# capacitor.net
KiCad netlist of a schematic drawn in EAGLE
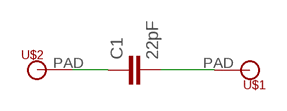
[diagram p0: schematic, sheet 1]

(export (version "E")
  (design (tool "Eeschema 10.0.6"))
  (components
    (comp (ref "C1")
      (value "22pF")
      (footprint "eagle-import:CAP-PTH-2.54")
      (libsource (lib "eagle-import") (part "22PF-PTH-2.54MM-200V-5%"))
    )
    (comp (ref "U$1")
      (value "MICROBIT_PAD")
      (footprint "eagle-import:MICROBIT_PAD")
      (libsource (lib "eagle-import") (part "MICROBIT_PAD"))
    )
    (comp (ref "U$2")
      (value "MICROBIT_PAD")
      (footprint "eagle-import:MICROBIT_PAD")
      (libsource (lib "eagle-import") (part "MICROBIT_PAD"))
    )
  )
  (nets
    (net (code "1") (name "Net-(U$1-P$1)") (class "Default")
      (node (ref "C1") (pin "2") (pinfunction "2_2") (pintype "passive"))
      (node (ref "U$1") (pin "PAD") (pinfunction "P$1_PAD") (pintype "bidirectional"))
    )
    (net (code "2") (name "Net-(U$2-P$1)") (class "Default")
      (node (ref "C1") (pin "1") (pinfunction "1_1") (pintype "passive"))
      (node (ref "U$2") (pin "PAD") (pinfunction "P$1_PAD") (pintype "bidirectional"))
    )
  )
)
